# FETs.net
KiCad netlist of a schematic drawn in Altium Designer
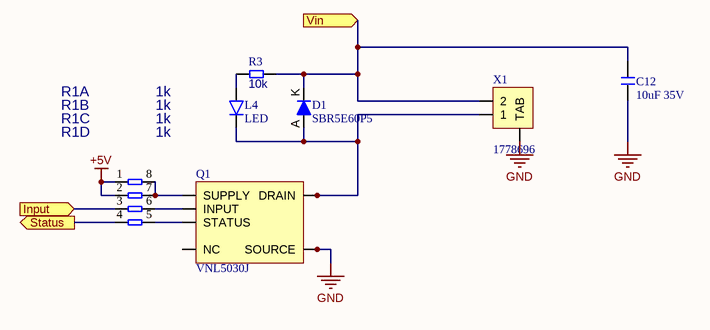
[diagram p0: FETs.SchDoc]

(export (version "E")
  (design (tool "Eeschema 10.0.6"))
  (components
    (comp (ref "C12")
      (value "10uF 35V")
      (footprint "C1210_N")
      (description "Capacitor MLCC")
      (fields
        (field (name "MANUFACTURER") "Yageo")
        (field (name "MANUFACTURER PART NUMBER") "CC0603KRX7R9BB104")
      )
      (libsource (lib "wes") (part "Capacitor"))
    )
    (comp (ref "D1") (value "SBR5E60P5") (footprint "PowerDI5") (libsource (lib "wes") (part "Diode")))
    (comp (ref "L4") (value "LED") (footprint "LED 0603 Reverse") (libsource (lib "wes") (part "LED")))
    (comp (ref "Q1") (value "VNL5030J") (footprint "PowerSSO-12") (libsource (lib "wes") (part "VNL5030JTR")))
    (comp (ref "R1") (value "1k") (footprint "YC164") (libsource (lib "wes") (part "Resistor Array - 4P")))
    (comp (ref "R3")
      (value "10k")
      (footprint "R0603")
      (fields (field (name "PUBLISHER") "Altium Limited"))
      (libsource (lib "wes") (part "Resistor"))
    )
    (comp (ref "X1")
      (value "1778696")
      (footprint "PTSM-2W-V-SMD")
      (libsource (lib "wes") (part "Connector 2W - TAB"))
    )
  )
  (nets
    (net (code "1") (name "+5V") (class "Default")
      (node (ref "R1") (pin "1") (pinfunction "1_1") (pintype "passive"))
      (node (ref "R1") (pin "2") (pinfunction "2_2") (pintype "passive"))
    )
    (net (code "2") (name "/Input") (class "Default")
      (node (ref "R1") (pin "3") (pinfunction "3_3") (pintype "passive"))
    )
    (net (code "3") (name "/Status") (class "Default")
      (node (ref "R1") (pin "4") (pinfunction "4_4") (pintype "passive"))
    )
    (net (code "4") (name "/Vin") (class "Default")
      (node (ref "C12") (pin "1") (pintype "passive"))
      (node (ref "D1") (pin "K") (pinfunction "K_K") (pintype "passive"))
      (node (ref "R3") (pin "2") (pinfunction "2_2") (pintype "passive"))
      (node (ref "X1") (pin "2") (pinfunction "2_2") (pintype "passive"))
    )
    (net (code "5") (name "GND") (class "Default")
      (node (ref "C12") (pin "2") (pintype "passive"))
      (node (ref "Q1") (pin "10") (pinfunction "SOURCE_10") (pintype "power_in"))
      (node (ref "Q1") (pin "11") (pinfunction "SOURCE_11") (pintype "power_in"))
      (node (ref "Q1") (pin "12") (pinfunction "SOURCE_12") (pintype "power_in"))
      (node (ref "Q1") (pin "7") (pinfunction "SOURCE_7") (pintype "power_in"))
      (node (ref "Q1") (pin "8") (pinfunction "SOURCE_8") (pintype "power_in"))
      (node (ref "Q1") (pin "9") (pinfunction "SOURCE_9") (pintype "power_in"))
      (node (ref "X1") (pin "TAB") (pinfunction "TAB_TAB") (pintype "power_in"))
    )
    (net (code "6") (name "Net-(L4-A)") (class "Default")
      (node (ref "L4") (pin "2") (pinfunction "A_2") (pintype "power_in"))
      (node (ref "R3") (pin "1") (pinfunction "1_1") (pintype "passive"))
    )
    (net (code "7") (name "Net-(L4-K)") (class "Default")
      (node (ref "D1") (pin "A") (pinfunction "A_A") (pintype "passive"))
      (node (ref "L4") (pin "1") (pinfunction "K_1") (pintype "power_in"))
      (node (ref "Q1") (pin "1") (pinfunction "DRAIN_1") (pintype "power_in"))
      (node (ref "Q1") (pin "6") (pinfunction "DRAIN_6") (pintype "power_in"))
      (node (ref "Q1") (pin "PAD") (pinfunction "DRAIN_PAD") (pintype "power_in"))
      (node (ref "X1") (pin "1") (pinfunction "1_1") (pintype "passive"))
    )
    (net (code "8") (name "Net-(Q1-INPUT)") (class "Default")
      (node (ref "Q1") (pin "3") (pinfunction "INPUT_3") (pintype "passive"))
      (node (ref "R1") (pin "6") (pinfunction "6_6") (pintype "passive"))
    )
    (net (code "9") (name "Net-(Q1-STATUS)") (class "Default")
      (node (ref "Q1") (pin "4") (pinfunction "STATUS_4") (pintype "passive"))
      (node (ref "R1") (pin "5") (pinfunction "5_5") (pintype "passive"))
    )
    (net (code "10") (name "Net-(Q1-SUPPLY)") (class "Default")
      (node (ref "Q1") (pin "2") (pinfunction "SUPPLY_2") (pintype "passive"))
      (node (ref "R1") (pin "7") (pinfunction "7_7") (pintype "passive"))
      (node (ref "R1") (pin "8") (pinfunction "8_8") (pintype "passive"))
    )
    (net (code "11") (name "unconnected-(Q1-NC-Pad5)") (class "Default")
      (node (ref "Q1") (pin "5") (pinfunction "NC_5") (pintype "power_in"))
    )
  )
)
